# HAM-LM_V2_7E.net
KiCad netlist of a schematic drawn in EasyEDA
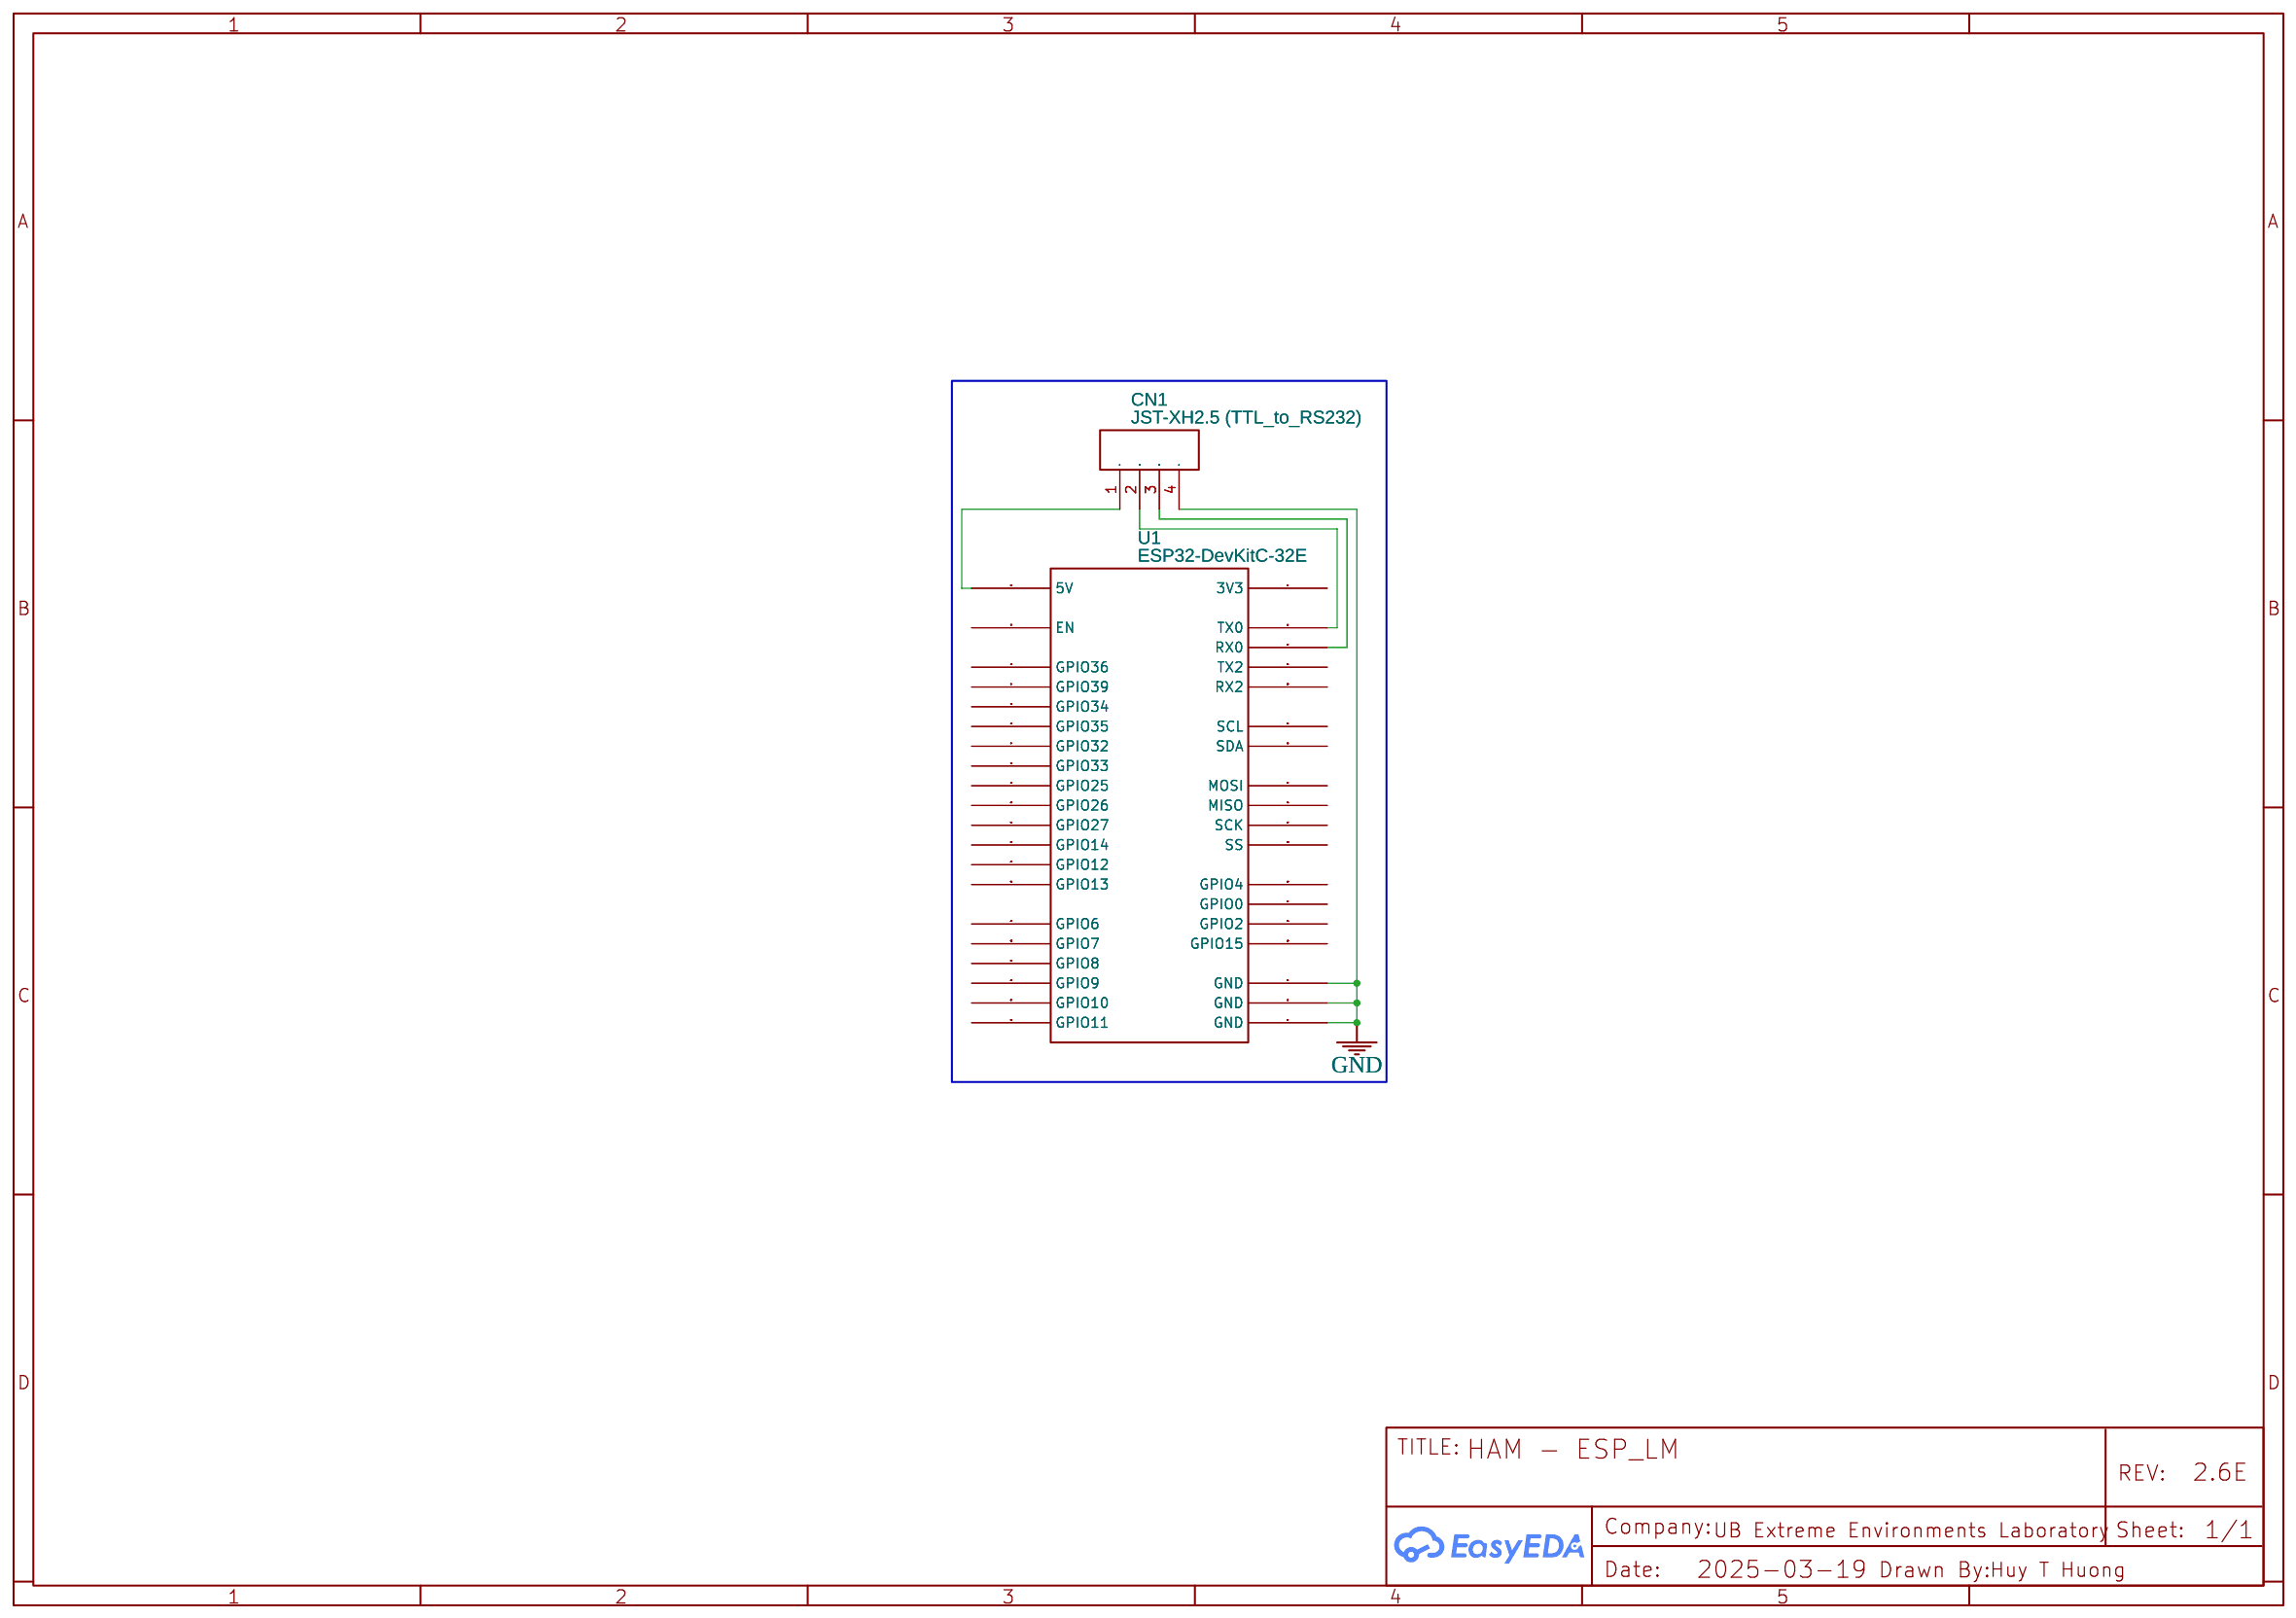
[diagram p0: schematic sheet]

(export (version "E")
  (design (tool "Eeschema 10.0.6"))
  (components
    (comp (ref "CN1")
      (value "JST-XH2.5 (TTL_to_RS232)")
      (libsource (lib "") (part "JST-XH2.54- 4 PIN Y COPY"))
    )
    (comp (ref "U1")
      (value "ESP32-DevKitC-32E")
      (fields (field (name "Manufacturer") "Espressif Systems"))
      (libsource (lib "") (part "ESP32-DevKitC-32E"))
    )
  )
  (nets
    (net (code "1") (name "GND") (class "Default")
      (node (ref "CN1") (pin "4") (pinfunction "4_4") (pintype "unspecified"))
      (node (ref "U1") (pin "J1_14") (pinfunction "GND_J1_14") (pintype "passive"))
      (node (ref "U1") (pin "J3_1") (pinfunction "GND_J3_1") (pintype "passive"))
      (node (ref "U1") (pin "J3_7") (pinfunction "GND_J3_7") (pintype "passive"))
    )
    (net (code "2") (name "Net-(U1-5V)") (class "Default")
      (node (ref "CN1") (pin "1") (pinfunction "1_1") (pintype "unspecified"))
      (node (ref "U1") (pin "J1_19") (pinfunction "5V_J1_19") (pintype "passive"))
    )
    (net (code "3") (name "Net-(U1-RX0)") (class "Default")
      (node (ref "CN1") (pin "3") (pinfunction "3_3") (pintype "unspecified"))
      (node (ref "U1") (pin "J3_5") (pinfunction "RX0_J3_5") (pintype "unspecified"))
    )
    (net (code "4") (name "Net-(U1-TX0)") (class "Default")
      (node (ref "CN1") (pin "2") (pinfunction "2_2") (pintype "unspecified"))
      (node (ref "U1") (pin "J3_4") (pinfunction "TX0_J3_4") (pintype "unspecified"))
    )
    (net (code "5") (name "unconnected-(U1-3V3-PadJ1_1)") (class "Default")
      (node (ref "U1") (pin "J1_1") (pinfunction "3V3_J1_1") (pintype "passive"))
    )
    (net (code "6") (name "unconnected-(U1-EN-PadJ1_2)") (class "Default")
      (node (ref "U1") (pin "J1_2") (pinfunction "EN_J1_2") (pintype "input"))
    )
    (net (code "7") (name "unconnected-(U1-GPIO0-PadJ3_14)") (class "Default")
      (node (ref "U1") (pin "J3_14") (pinfunction "GPIO0_J3_14") (pintype "bidirectional"))
    )
    (net (code "8") (name "unconnected-(U1-GPIO2-PadJ3_15)") (class "Default")
      (node (ref "U1") (pin "J3_15") (pinfunction "GPIO2_J3_15") (pintype "bidirectional"))
    )
    (net (code "9") (name "unconnected-(U1-GPIO4-PadJ3_13)") (class "Default")
      (node (ref "U1") (pin "J3_13") (pinfunction "GPIO4_J3_13") (pintype "bidirectional"))
    )
    (net (code "10") (name "unconnected-(U1-GPIO6-PadJ3_19)") (class "Default")
      (node (ref "U1") (pin "J3_19") (pinfunction "GPIO6_J3_19") (pintype "bidirectional"))
    )
    (net (code "11") (name "unconnected-(U1-GPIO7-PadJ3_18)") (class "Default")
      (node (ref "U1") (pin "J3_18") (pinfunction "GPIO7_J3_18") (pintype "bidirectional"))
    )
    (net (code "12") (name "unconnected-(U1-GPIO8-PadJ3_17)") (class "Default")
      (node (ref "U1") (pin "J3_17") (pinfunction "GPIO8_J3_17") (pintype "bidirectional"))
    )
    (net (code "13") (name "unconnected-(U1-GPIO9-PadJ1_16)") (class "Default")
      (node (ref "U1") (pin "J1_16") (pinfunction "GPIO9_J1_16") (pintype "bidirectional"))
    )
    (net (code "14") (name "unconnected-(U1-GPIO10-PadJ1_17)") (class "Default")
      (node (ref "U1") (pin "J1_17") (pinfunction "GPIO10_J1_17") (pintype "bidirectional"))
    )
    (net (code "15") (name "unconnected-(U1-GPIO11-PadJ1_18)") (class "Default")
      (node (ref "U1") (pin "J1_18") (pinfunction "GPIO11_J1_18") (pintype "bidirectional"))
    )
    (net (code "16") (name "unconnected-(U1-GPIO12-PadJ1_13)") (class "Default")
      (node (ref "U1") (pin "J1_13") (pinfunction "GPIO12_J1_13") (pintype "bidirectional"))
    )
    (net (code "17") (name "unconnected-(U1-GPIO13-PadJ1_15)") (class "Default")
      (node (ref "U1") (pin "J1_15") (pinfunction "GPIO13_J1_15") (pintype "bidirectional"))
    )
    (net (code "18") (name "unconnected-(U1-GPIO14-PadJ1_12)") (class "Default")
      (node (ref "U1") (pin "J1_12") (pinfunction "GPIO14_J1_12") (pintype "bidirectional"))
    )
    (net (code "19") (name "unconnected-(U1-GPIO15-PadJ3_16)") (class "Default")
      (node (ref "U1") (pin "J3_16") (pinfunction "GPIO15_J3_16") (pintype "bidirectional"))
    )
    (net (code "20") (name "unconnected-(U1-GPIO25-PadJ1_9)") (class "Default")
      (node (ref "U1") (pin "J1_9") (pinfunction "GPIO25_J1_9") (pintype "bidirectional"))
    )
    (net (code "21") (name "unconnected-(U1-GPIO26-PadJ1_10)") (class "Default")
      (node (ref "U1") (pin "J1_10") (pinfunction "GPIO26_J1_10") (pintype "bidirectional"))
    )
    (net (code "22") (name "unconnected-(U1-GPIO27-PadJ1_11)") (class "Default")
      (node (ref "U1") (pin "J1_11") (pinfunction "GPIO27_J1_11") (pintype "bidirectional"))
    )
    (net (code "23") (name "unconnected-(U1-GPIO32-PadJ1_7)") (class "Default")
      (node (ref "U1") (pin "J1_7") (pinfunction "GPIO32_J1_7") (pintype "bidirectional"))
    )
    (net (code "24") (name "unconnected-(U1-GPIO33-PadJ1_8)") (class "Default")
      (node (ref "U1") (pin "J1_8") (pinfunction "GPIO33_J1_8") (pintype "bidirectional"))
    )
    (net (code "25") (name "unconnected-(U1-GPIO34-PadJ1_5)") (class "Default")
      (node (ref "U1") (pin "J1_5") (pinfunction "GPIO34_J1_5") (pintype "bidirectional"))
    )
    (net (code "26") (name "unconnected-(U1-GPIO35-PadJ1_6)") (class "Default")
      (node (ref "U1") (pin "J1_6") (pinfunction "GPIO35_J1_6") (pintype "bidirectional"))
    )
    (net (code "27") (name "unconnected-(U1-GPIO36-PadJ1_3)") (class "Default")
      (node (ref "U1") (pin "J1_3") (pinfunction "GPIO36_J1_3") (pintype "bidirectional"))
    )
    (net (code "28") (name "unconnected-(U1-GPIO39-PadJ1_4)") (class "Default")
      (node (ref "U1") (pin "J1_4") (pinfunction "GPIO39_J1_4") (pintype "bidirectional"))
    )
    (net (code "29") (name "unconnected-(U1-MISO-PadJ3_8)") (class "Default")
      (node (ref "U1") (pin "J3_8") (pinfunction "MISO_J3_8") (pintype "unspecified"))
    )
    (net (code "30") (name "unconnected-(U1-MOSI-PadJ3_2)") (class "Default")
      (node (ref "U1") (pin "J3_2") (pinfunction "MOSI_J3_2") (pintype "unspecified"))
    )
    (net (code "31") (name "unconnected-(U1-RX2-PadJ3_12)") (class "Default")
      (node (ref "U1") (pin "J3_12") (pinfunction "RX2_J3_12") (pintype "unspecified"))
    )
    (net (code "32") (name "unconnected-(U1-SCK-PadJ3_9)") (class "Default")
      (node (ref "U1") (pin "J3_9") (pinfunction "SCK_J3_9") (pintype "unspecified"))
    )
    (net (code "33") (name "unconnected-(U1-SCL-PadJ3_3)") (class "Default")
      (node (ref "U1") (pin "J3_3") (pinfunction "SCL_J3_3") (pintype "unspecified"))
    )
    (net (code "34") (name "unconnected-(U1-SDA-PadJ3_6)") (class "Default")
      (node (ref "U1") (pin "J3_6") (pinfunction "SDA_J3_6") (pintype "unspecified"))
    )
    (net (code "35") (name "unconnected-(U1-SS-PadJ3_10)") (class "Default")
      (node (ref "U1") (pin "J3_10") (pinfunction "SS_J3_10") (pintype "unspecified"))
    )
    (net (code "36") (name "unconnected-(U1-TX2-PadJ3_11)") (class "Default")
      (node (ref "U1") (pin "J3_11") (pinfunction "TX2_J3_11") (pintype "unspecified"))
    )
  )
)
